# Kicker2018.net
KiCad netlist of a schematic drawn in Altium Designer
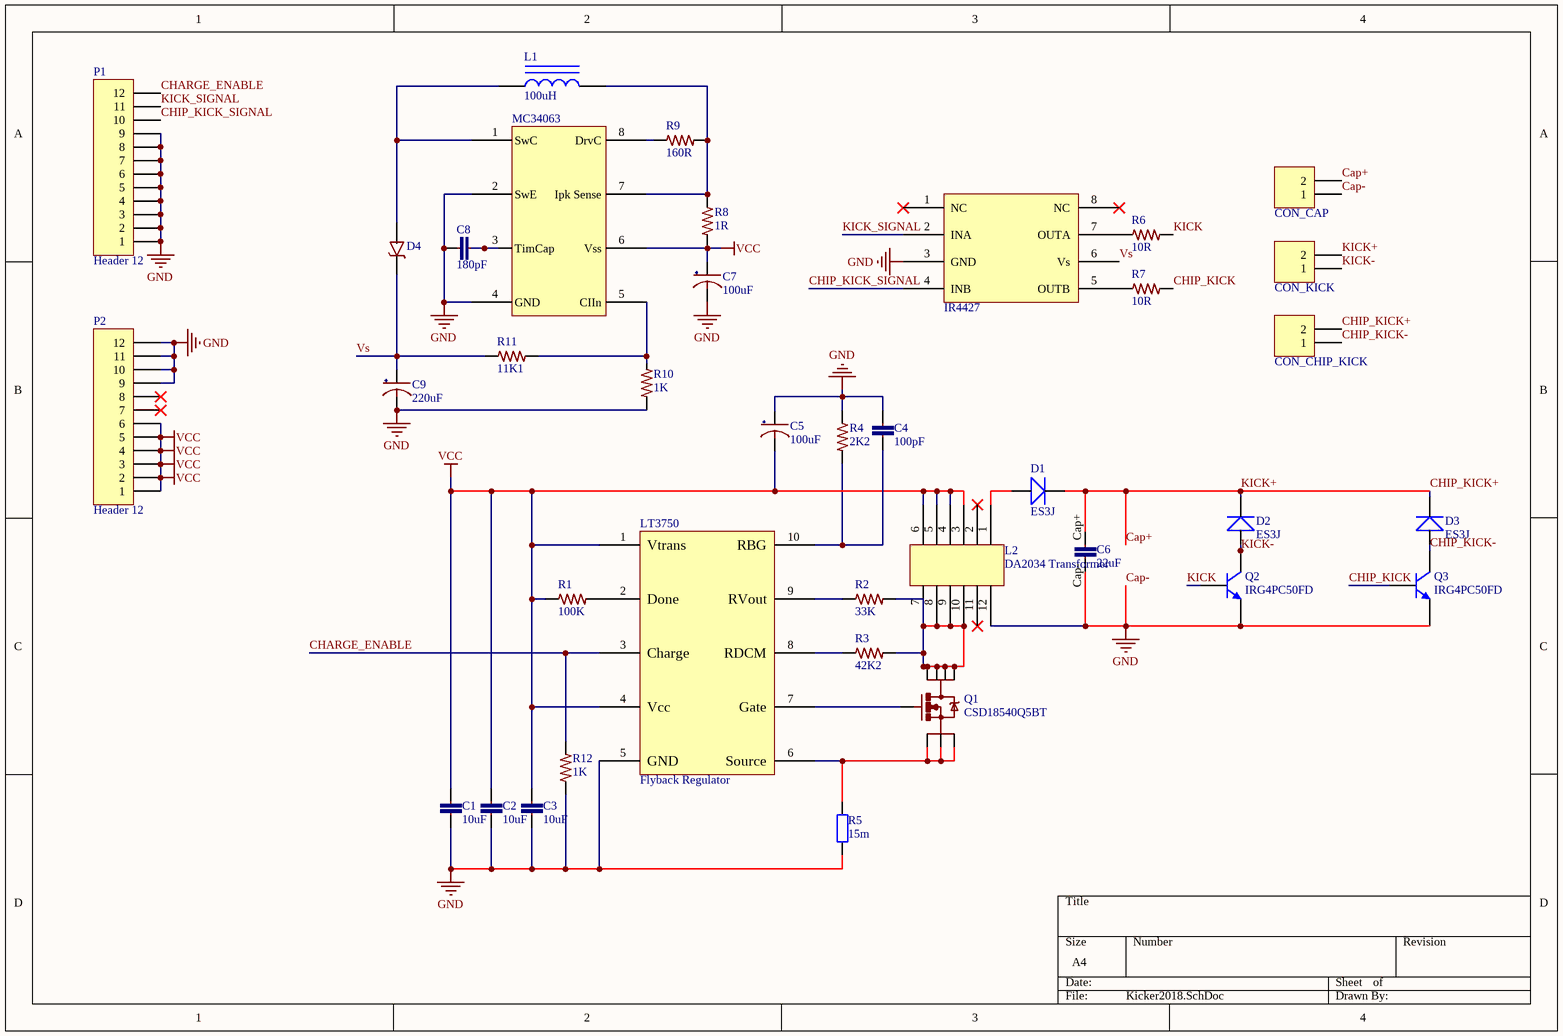
[diagram p0: Kicker2018.SchDoc]

(export (version "E")
  (design (tool "Eeschema 10.0.6"))
  (components
    (comp (ref "C1")
      (value "10uF")
      (footprint "CAPC0603(1608)55_L")
      (description "CAP CER 10UF 16V X5R 0603")
      (fields (field (name "PART NO") "EMK107BBJ106MA-T"))
      (libsource (lib "IMBEL") (part "CAPACITOR"))
    )
    (comp (ref "C2")
      (value "10uF")
      (footprint "CAPC0603(1608)55_L")
      (description "CAP CER 10UF 16V X5R 0603")
      (fields (field (name "PART NO") "EMK107BBJ106MA-T"))
      (libsource (lib "IMBEL") (part "CAPACITOR"))
    )
    (comp (ref "C3")
      (value "10uF")
      (footprint "CAPC0603(1608)55_L")
      (description "CAP CER 10UF 16V X5R 0603")
      (fields (field (name "PART NO") "EMK107BBJ106MA-T"))
      (libsource (lib "IMBEL") (part "CAPACITOR"))
    )
    (comp (ref "C4")
      (value "100pF")
      (footprint "CAPC0603(1608)55_L")
      (description "CAP CER 100PF 50V NP0 0603")
      (fields (field (name "PART NO") "GRM1885C1H101JA01D"))
      (libsource (lib "IMBEL") (part "CAPACITOR"))
    )
    (comp (ref "C5")
      (value "100uF")
      (footprint "PCBComponent")
      (description "CAP ALUM 100UF 20% 80V SMD")
      (libsource (lib "IMBEL") (part "CAPACITOR-POL"))
    )
    (comp (ref "C6")
      (value "22uF")
      (footprint "CAP ALUM 22UF 250V")
      (libsource (lib "Schlib1") (part "CAP ALUM 22UF 250V"))
    )
    (comp (ref "C7")
      (value "100uF")
      (footprint "7343-CAPPOL")
      (description "CAP TANT 100uF 25V 20% ESR = 30mOhm @ 100 kHz")
      (fields (field (name "PART NO") "T521X107M025ATE030"))
      (libsource (lib "IMBEL") (part "CT2917-100uF-1"))
    )
    (comp (ref "C8")
      (value "180pF")
      (footprint "0805-CAP")
      (description "CAP CER 180PF 50V NP0 0805")
      (fields (field (name "PART NO") "C0805C181K5GACTU"))
      (libsource (lib "IMBEL") (part "CC0805-180pF-2"))
    )
    (comp (ref "C9")
      (value "220uF")
      (footprint "NIC-CAPA2-10X10_V")
      (description "CAP ALUM 220uF 20% 50V  ESR = 0,18 ohms  Radial DIA 10mm HEIGH 10,2mm")
      (fields (field (name "PART NO") "EEEFK1H221P"))
      (libsource (lib "IMBEL") (part "CAPACITOR-POL"))
    )
    (comp (ref "CON_CAP")
      (value "OSTTA024163")
      (footprint "Term Block 2P")
      (description "2 Position Wire to Board Terminal Block Horizontal with Board 0.200\" (5.08mm) Through Hole")
      (libsource (lib "Schlib1") (part "Term Block 2P"))
    )
    (comp (ref "CON_CHIP_KICK")
      (value "OSTTA024163")
      (footprint "Term Block 2P")
      (description "2 Position Wire to Board Terminal Block Horizontal with Board 0.200\" (5.08mm) Through Hole")
      (libsource (lib "Schlib1") (part "Term Block 2P"))
    )
    (comp (ref "CON_KICK")
      (value "OSTTA024163")
      (footprint "Term Block 2P")
      (description "2 Position Wire to Board Terminal Block Horizontal with Board 0.200\" (5.08mm) Through Hole")
      (libsource (lib "Schlib1") (part "Term Block 2P"))
    )
    (comp (ref "D1") (value "ES3J") (footprint "Diode") (libsource (lib "KickerSchlib") (part "ES3J")))
    (comp (ref "D2") (value "ES3J") (footprint "Diode") (libsource (lib "KickerSchlib") (part "ES3J")))
    (comp (ref "D3") (value "ES3J") (footprint "Diode") (libsource (lib "KickerSchlib") (part "ES3J")))
    (comp (ref "D4")
      (value "DIODE SCHOTTKY 60V 30A D2PAK")
      (footprint "DPAK254P1542X460-3N")
      (fields (field (name "PART NO") "STPS30M60SG-TR"))
      (libsource (lib "IMBEL") (part "STPS30M60SG-TR-1"))
    )
    (comp (ref "IR4427")
      (value "GATE DRIVER")
      (footprint "IR4427")
      (description "IC DRIVER DUAL LOW SIDE 8-SOIC")
      (libsource (lib "KickerSchlib") (part "IR4427"))
    )
    (comp (ref "L1")
      (value "100uH")
      (footprint "INDUCTOR")
      (description "Fixed Inductors 100uH 0.86A SMT")
      (libsource (lib "KickerSchlib") (part "Inductor"))
    )
    (comp (ref "L2")
      (value "DA2034 Transformer")
      (footprint "DA2034 Transformer")
      (libsource (lib "KickerSchlib") (part "DA2034 Transformer"))
    )
    (comp (ref "LT3750")
      (value "Flyback Regulator")
      (footprint "LT3750")
      (libsource (lib "KickerSchlib") (part "LT3750"))
    )
    (comp (ref "MC34063")
      (value "Switching Voltage Regulator")
      (footprint "MC34063")
      (libsource (lib "Schlib1") (part "MC34063"))
    )
    (comp (ref "P1")
      (value "Header 12")
      (footprint "HDR1X12")
      (description "Header, 12-Pin")
      (fields (field (name "PUBLISHER") "Altium Limited"))
      (libsource (lib "Miscellaneous Connectors") (part "Header 12"))
    )
    (comp (ref "P2")
      (value "Header 12")
      (footprint "HDR1X12")
      (description "Header, 12-Pin")
      (fields (field (name "PUBLISHER") "Altium Limited"))
      (libsource (lib "Miscellaneous Connectors") (part "Header 12"))
    )
    (comp (ref "Q1")
      (value "CSD18540Q5BT")
      (footprint "PCBComponent")
      (description "MOSFET N-CH 60V 100A 8VSON")
      (libsource (lib "IMBEL") (part "MOSFET-NCHANNEL"))
    )
    (comp (ref "Q2")
      (value "IRG4PC50FD")
      (footprint "IRG4PC50FD")
      (description "IGBT Transistors 600V FAST 1-8 KHZ COPACK IGBT")
      (fields (field (name "PUBLISHER") "RoboIME"))
      (libsource (lib "KickerSchlib") (part "IRG4PC50FD"))
    )
    (comp (ref "Q3")
      (value "IRG4PC50FD")
      (footprint "IRG4PC50FD")
      (description "IGBT Transistors 600V FAST 1-8 KHZ COPACK IGBT")
      (fields (field (name "PUBLISHER") "RoboIME"))
      (libsource (lib "KickerSchlib") (part "IRG4PC50FD"))
    )
    (comp (ref "R1")
      (value "100K")
      (footprint "0402-RES-HD")
      (description "RES 100K OHM 1/10W 1% 0402 SMD 1")
      (fields (field (name "PART NO") "ERJ-2GEJ104X"))
      (libsource (lib "IMBEL") (part "RESISTOR"))
    )
    (comp (ref "R2")
      (value "33K")
      (footprint "0402-RES-HD")
      (description "RES 33K OHM 1/10W 1% 0402 SMD")
      (fields (field (name "PART NO") "ERJ-2RKF3302X"))
      (libsource (lib "IMBEL") (part "RESISTOR"))
    )
    (comp (ref "R3")
      (value "42K2")
      (footprint "0402-RES-HD")
      (description "RES 42.2K OHM 1/10W 1% 0402 SMD")
      (fields (field (name "PART NO") "ERJ-2RKF4222X"))
      (libsource (lib "Schlib1") (part "RESISTOR"))
    )
    (comp (ref "R4")
      (value "2K2")
      (footprint "0402-RES-HD")
      (description "RES 2.2K OHM 1/10W 1% 0402 SMD")
      (fields (field (name "PART NO") "ERJ-2RKF2201X"))
      (libsource (lib "IMBEL") (part "RESISTOR"))
    )
    (comp (ref "R5")
      (value "15m")
      (footprint "RES1206")
      (description "Resistor")
      (fields (field (name "PUBLISHER") "Altium Limited"))
      (libsource (lib "Schlib1") (part "Res2"))
    )
    (comp (ref "R6")
      (value "10R")
      (footprint "0402-RES-HD")
      (description "RES 10 OHM 1/10W 1% 0402 SMD")
      (fields (field (name "PART NO") "ERJ-2RKF10R0X"))
      (libsource (lib "IMBEL") (part "RESISTOR"))
    )
    (comp (ref "R7")
      (value "10R")
      (footprint "0402-RES-HD")
      (description "RES 10 OHM 1/10W 1% 0402 SMD")
      (fields (field (name "PART NO") "ERJ-2RKF10R0X"))
      (libsource (lib "IMBEL") (part "RESISTOR"))
    )
    (comp (ref "R8")
      (value "1R")
      (footprint "0805-RES")
      (description "RES SMD 1 OHM 1% 1/8W 0805")
      (fields (field (name "PART NO") "CRCW08051R00FKEA"))
      (libsource (lib "IMBEL") (part "R0805-1R-1%-1"))
    )
    (comp (ref "R9")
      (value "160R")
      (footprint "0805-RES")
      (description "RES 160 OHM 1/8W .5% 0805 SMD")
      (fields (field (name "PART NO") "ERA-6AED161V"))
      (libsource (lib "IMBEL") (part "R0805-160R-5"))
    )
    (comp (ref "R10")
      (value "1K")
      (footprint "0402-RES-HD")
      (description "RES 1K OHM 1/10W 1% 0402 SMD")
      (fields (field (name "PART NO") "ERJ-2RKF1001X"))
      (libsource (lib "IMBEL") (part "R0402-1K-A.9"))
    )
    (comp (ref "R11")
      (value "11K1")
      (footprint "0402-RES-HD")
      (description "RES 11.1 KOHM 1/16W 0.1% 0402 SMD")
      (fields (field (name "PART NO") "TNPW040211K1BEED"))
      (libsource (lib "IMBEL") (part "R0402-11K1-1"))
    )
    (comp (ref "R12")
      (value "1K")
      (footprint "0402-RES-HD")
      (description "RES 1K OHM 1/10W 1% 0402 SMD")
      (fields (field (name "PART NO") "ERJ-2RKF1001X"))
      (libsource (lib "IMBEL") (part "RESISTOR"))
    )
  )
  (nets
    (net (code "1") (name "/CHARGE_ENABLE") (class "Default")
      (node (ref "LT3750") (pin "3") (pinfunction "Charge_3") (pintype "passive"))
      (node (ref "P1") (pin "12") (pinfunction "12_12") (pintype "passive"))
      (node (ref "R12") (pin "2") (pinfunction "2_2") (pintype "passive"))
    )
    (net (code "2") (name "/CHIP_KICK") (class "Default")
      (node (ref "Q3") (pin "2") (pinfunction "G_2") (pintype "passive"))
      (node (ref "R7") (pin "2") (pinfunction "2_2") (pintype "passive"))
    )
    (net (code "3") (name "/CHIP_KICK+") (class "Default")
      (node (ref "C6") (pin "Cap+") (pinfunction "Cap+_Cap+") (pintype "passive"))
      (node (ref "CON_CAP") (pin "2") (pinfunction "2_2") (pintype "passive"))
      (node (ref "CON_CHIP_KICK") (pin "2") (pinfunction "2_2") (pintype "passive"))
      (node (ref "CON_KICK") (pin "2") (pinfunction "2_2") (pintype "passive"))
      (node (ref "D1") (pin "D1+") (pinfunction "D1+_D1+") (pintype "passive"))
      (node (ref "D2") (pin "D1+") (pinfunction "D1+_D1+") (pintype "passive"))
      (node (ref "D3") (pin "D1+") (pinfunction "D1+_D1+") (pintype "passive"))
    )
    (net (code "4") (name "/CHIP_KICK-") (class "Default")
      (node (ref "CON_CHIP_KICK") (pin "1") (pinfunction "1_1") (pintype "passive"))
      (node (ref "D3") (pin "D1-") (pinfunction "D1-_D1-") (pintype "passive"))
      (node (ref "Q3") (pin "1") (pinfunction "C_1") (pintype "passive"))
    )
    (net (code "5") (name "/CHIP_KICK_SIGNAL") (class "Default")
      (node (ref "IR4427") (pin "4") (pinfunction "INB_4") (pintype "passive"))
      (node (ref "P1") (pin "10") (pinfunction "10_10") (pintype "passive"))
    )
    (net (code "6") (name "/KICK") (class "Default")
      (node (ref "Q2") (pin "2") (pinfunction "G_2") (pintype "passive"))
      (node (ref "R6") (pin "2") (pinfunction "2_2") (pintype "passive"))
    )
    (net (code "7") (name "/KICK-") (class "Default")
      (node (ref "CON_KICK") (pin "1") (pinfunction "1_1") (pintype "passive"))
      (node (ref "D2") (pin "D1-") (pinfunction "D1-_D1-") (pintype "passive"))
      (node (ref "Q2") (pin "1") (pinfunction "C_1") (pintype "passive"))
    )
    (net (code "8") (name "/KICK_SIGNAL") (class "Default")
      (node (ref "IR4427") (pin "2") (pinfunction "INA_2") (pintype "passive"))
      (node (ref "P1") (pin "11") (pinfunction "11_11") (pintype "passive"))
    )
    (net (code "9") (name "/Vs") (class "Default")
      (node (ref "C9") (pin "1") (pinfunction "+_1") (pintype "passive"))
      (node (ref "D4") (pin "K") (pinfunction "K_K") (pintype "passive"))
      (node (ref "IR4427") (pin "6") (pinfunction "Vs_6") (pintype "passive"))
      (node (ref "R11") (pin "1") (pinfunction "1_1") (pintype "passive"))
    )
    (net (code "10") (name "GND") (class "Default")
      (node (ref "C1") (pin "2") (pinfunction "2_2") (pintype "passive"))
      (node (ref "C2") (pin "2") (pinfunction "2_2") (pintype "passive"))
      (node (ref "C3") (pin "2") (pinfunction "2_2") (pintype "passive"))
      (node (ref "C4") (pin "1") (pinfunction "1_1") (pintype "passive"))
      (node (ref "C5") (pin "1") (pinfunction "+_1") (pintype "passive"))
      (node (ref "C6") (pin "Cap-") (pinfunction "Cap-_Cap-") (pintype "passive"))
      (node (ref "C7") (pin "2") (pinfunction "-_2") (pintype "passive"))
      (node (ref "C8") (pin "1") (pinfunction "1_1") (pintype "passive"))
      (node (ref "C9") (pin "2") (pinfunction "-_2") (pintype "passive"))
      (node (ref "CON_CAP") (pin "1") (pinfunction "1_1") (pintype "passive"))
      (node (ref "IR4427") (pin "3") (pinfunction "GND_3") (pintype "passive"))
      (node (ref "L2") (pin "12") (pinfunction "12_12") (pintype "passive"))
      (node (ref "LT3750") (pin "5") (pinfunction "GND_5") (pintype "passive"))
      (node (ref "MC34063") (pin "2") (pinfunction "SwE_2") (pintype "passive"))
      (node (ref "MC34063") (pin "4") (pinfunction "GND_4") (pintype "passive"))
      (node (ref "P1") (pin "1") (pinfunction "1_1") (pintype "passive"))
      (node (ref "P1") (pin "2") (pinfunction "2_2") (pintype "passive"))
      (node (ref "P1") (pin "3") (pinfunction "3_3") (pintype "passive"))
      (node (ref "P1") (pin "4") (pinfunction "4_4") (pintype "passive"))
      (node (ref "P1") (pin "5") (pinfunction "5_5") (pintype "passive"))
      (node (ref "P1") (pin "6") (pinfunction "6_6") (pintype "passive"))
      (node (ref "P1") (pin "7") (pinfunction "7_7") (pintype "passive"))
      (node (ref "P1") (pin "8") (pinfunction "8_8") (pintype "passive"))
      (node (ref "P1") (pin "9") (pinfunction "9_9") (pintype "passive"))
      (node (ref "P2") (pin "10") (pinfunction "10_10") (pintype "passive"))
      (node (ref "P2") (pin "11") (pinfunction "11_11") (pintype "passive"))
      (node (ref "P2") (pin "12") (pinfunction "12_12") (pintype "passive"))
      (node (ref "P2") (pin "9") (pinfunction "9_9") (pintype "passive"))
      (node (ref "Q2") (pin "3") (pinfunction "E_3") (pintype "passive"))
      (node (ref "Q3") (pin "3") (pinfunction "E_3") (pintype "passive"))
      (node (ref "R10") (pin "1") (pinfunction "1_1") (pintype "passive"))
      (node (ref "R12") (pin "1") (pinfunction "1_1") (pintype "passive"))
      (node (ref "R4") (pin "2") (pinfunction "2_2") (pintype "passive"))
      (node (ref "R5") (pin "2") (pinfunction "2_2") (pintype "passive"))
    )
    (net (code "11") (name "Net-(D1-PadD1-)") (class "Default")
      (node (ref "D1") (pin "D1-") (pinfunction "D1-_D1-") (pintype "passive"))
      (node (ref "L2") (pin "1") (pinfunction "1_1") (pintype "passive"))
    )
    (net (code "12") (name "Net-(IR4427-OUTA)") (class "Default")
      (node (ref "IR4427") (pin "7") (pinfunction "OUTA_7") (pintype "passive"))
      (node (ref "R6") (pin "1") (pinfunction "1_1") (pintype "passive"))
    )
    (net (code "13") (name "Net-(IR4427-OUTB)") (class "Default")
      (node (ref "IR4427") (pin "5") (pinfunction "OUTB_5") (pintype "passive"))
      (node (ref "R7") (pin "1") (pinfunction "1_1") (pintype "passive"))
    )
    (net (code "14") (name "Net-(L2-Pad10)") (class "Default")
      (node (ref "L2") (pin "10") (pinfunction "10_10") (pintype "passive"))
      (node (ref "L2") (pin "7") (pinfunction "7_7") (pintype "passive"))
      (node (ref "L2") (pin "8") (pinfunction "8_8") (pintype "passive"))
      (node (ref "L2") (pin "9") (pinfunction "9_9") (pintype "passive"))
      (node (ref "Q1") (pin "5") (pinfunction "D_5") (pintype "passive"))
      (node (ref "Q1") (pin "6") (pinfunction "D_6") (pintype "passive"))
      (node (ref "Q1") (pin "7") (pinfunction "D_7") (pintype "passive"))
      (node (ref "Q1") (pin "8") (pinfunction "D_8") (pintype "passive"))
      (node (ref "R2") (pin "2") (pinfunction "2_2") (pintype "passive"))
      (node (ref "R3") (pin "2") (pinfunction "2_2") (pintype "passive"))
    )
    (net (code "15") (name "Net-(LT3750-Done)") (class "Default")
      (node (ref "LT3750") (pin "2") (pinfunction "Done_2") (pintype "passive"))
      (node (ref "R1") (pin "2") (pinfunction "2_2") (pintype "passive"))
    )
    (net (code "16") (name "Net-(LT3750-Gate)") (class "Default")
      (node (ref "LT3750") (pin "7") (pinfunction "Gate_7") (pintype "passive"))
      (node (ref "Q1") (pin "4") (pinfunction "G_4") (pintype "passive"))
    )
    (net (code "17") (name "Net-(LT3750-RBG)") (class "Default")
      (node (ref "C4") (pin "2") (pinfunction "2_2") (pintype "passive"))
      (node (ref "LT3750") (pin "10") (pinfunction "RBG_10") (pintype "passive"))
      (node (ref "R4") (pin "1") (pinfunction "1_1") (pintype "passive"))
    )
    (net (code "18") (name "Net-(LT3750-RDCM)") (class "Default")
      (node (ref "LT3750") (pin "8") (pinfunction "RDCM_8") (pintype "passive"))
      (node (ref "R3") (pin "1") (pinfunction "1_1") (pintype "passive"))
    )
    (net (code "19") (name "Net-(LT3750-RVout)") (class "Default")
      (node (ref "LT3750") (pin "9") (pinfunction "RVout_9") (pintype "passive"))
      (node (ref "R2") (pin "1") (pinfunction "1_1") (pintype "passive"))
    )
    (net (code "20") (name "Net-(LT3750-Source)") (class "Default")
      (node (ref "LT3750") (pin "6") (pinfunction "Source_6") (pintype "passive"))
      (node (ref "Q1") (pin "1") (pinfunction "S_1") (pintype "passive"))
      (node (ref "Q1") (pin "2") (pinfunction "S_2") (pintype "passive"))
      (node (ref "Q1") (pin "3") (pinfunction "S_3") (pintype "passive"))
      (node (ref "R5") (pin "1") (pinfunction "1_1") (pintype "passive"))
    )
    (net (code "21") (name "Net-(MC34063-CIIn)") (class "Default")
      (node (ref "MC34063") (pin "5") (pinfunction "CIIn_5") (pintype "passive"))
      (node (ref "R10") (pin "2") (pinfunction "2_2") (pintype "passive"))
      (node (ref "R11") (pin "2") (pinfunction "2_2") (pintype "passive"))
    )
    (net (code "22") (name "Net-(MC34063-DrvC)") (class "Default")
      (node (ref "MC34063") (pin "8") (pinfunction "DrvC_8") (pintype "passive"))
      (node (ref "R9") (pin "1") (pinfunction "1_1") (pintype "passive"))
    )
    (net (code "23") (name "Net-(MC34063-Ipk_Sense)") (class "Default")
      (node (ref "L1") (pin "2") (pinfunction "2_2") (pintype "passive"))
      (node (ref "MC34063") (pin "7") (pinfunction "Ipk_Sense_7") (pintype "passive"))
      (node (ref "R8") (pin "2") (pinfunction "2_2") (pintype "passive"))
      (node (ref "R9") (pin "2") (pinfunction "2_2") (pintype "passive"))
    )
    (net (code "24") (name "Net-(MC34063-SwC)") (class "Default")
      (node (ref "D4") (pin "A") (pinfunction "A_A") (pintype "passive"))
      (node (ref "L1") (pin "1") (pinfunction "1_1") (pintype "passive"))
      (node (ref "MC34063") (pin "1") (pinfunction "SwC_1") (pintype "passive"))
    )
    (net (code "25") (name "Net-(MC34063-TimCap)") (class "Default")
      (node (ref "C8") (pin "2") (pinfunction "2_2") (pintype "passive"))
      (node (ref "MC34063") (pin "3") (pinfunction "TimCap_3") (pintype "passive"))
    )
    (net (code "26") (name "VCC") (class "Default")
      (node (ref "C1") (pin "1") (pinfunction "1_1") (pintype "passive"))
      (node (ref "C2") (pin "1") (pinfunction "1_1") (pintype "passive"))
      (node (ref "C3") (pin "1") (pinfunction "1_1") (pintype "passive"))
      (node (ref "C5") (pin "2") (pinfunction "-_2") (pintype "passive"))
      (node (ref "C7") (pin "1") (pinfunction "+_1") (pintype "passive"))
      (node (ref "L2") (pin "3") (pinfunction "3_3") (pintype "passive"))
      (node (ref "L2") (pin "4") (pinfunction "4_4") (pintype "passive"))
      (node (ref "L2") (pin "5") (pinfunction "5_5") (pintype "passive"))
      (node (ref "L2") (pin "6") (pinfunction "6_6") (pintype "passive"))
      (node (ref "LT3750") (pin "1") (pinfunction "Vtrans_1") (pintype "passive"))
      (node (ref "LT3750") (pin "4") (pinfunction "Vcc_4") (pintype "passive"))
      (node (ref "MC34063") (pin "6") (pinfunction "Vss_6") (pintype "passive"))
      (node (ref "P2") (pin "1") (pinfunction "1_1") (pintype "passive"))
      (node (ref "P2") (pin "2") (pinfunction "2_2") (pintype "passive"))
      (node (ref "P2") (pin "3") (pinfunction "3_3") (pintype "passive"))
      (node (ref "P2") (pin "4") (pinfunction "4_4") (pintype "passive"))
      (node (ref "P2") (pin "5") (pinfunction "5_5") (pintype "passive"))
      (node (ref "P2") (pin "6") (pinfunction "6_6") (pintype "passive"))
      (node (ref "R1") (pin "1") (pinfunction "1_1") (pintype "passive"))
      (node (ref "R8") (pin "1") (pinfunction "1_1") (pintype "passive"))
    )
    (net (code "27") (name "unconnected-(IR4427-NC-Pad1)") (class "Default")
      (node (ref "IR4427") (pin "1") (pinfunction "NC_1") (pintype "passive+no_connect"))
    )
    (net (code "28") (name "unconnected-(IR4427-NC-Pad8)") (class "Default")
      (node (ref "IR4427") (pin "8") (pinfunction "NC_8") (pintype "passive+no_connect"))
    )
    (net (code "29") (name "unconnected-(L2-Pad2)") (class "Default")
      (node (ref "L2") (pin "2") (pinfunction "2_2") (pintype "passive+no_connect"))
    )
    (net (code "30") (name "unconnected-(L2-Pad11)") (class "Default")
      (node (ref "L2") (pin "11") (pinfunction "11_11") (pintype "passive+no_connect"))
    )
    (net (code "31") (name "unconnected-(P2-Pad7)") (class "Default")
      (node (ref "P2") (pin "7") (pinfunction "7_7") (pintype "passive+no_connect"))
    )
    (net (code "32") (name "unconnected-(P2-Pad8)") (class "Default")
      (node (ref "P2") (pin "8") (pinfunction "8_8") (pintype "passive+no_connect"))
    )
  )
)
